# CAN_Termination_Connector.net
KiCad netlist of a schematic drawn in Altium Designer
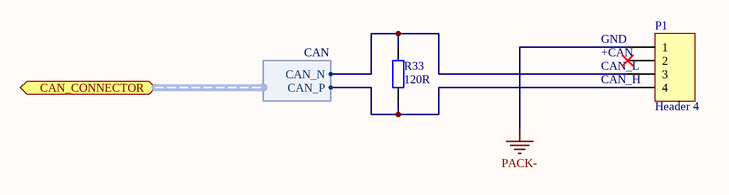
[diagram p0: CAN Termination Connector.SchDoc]

(export (version "E")
  (design (tool "Eeschema 10.0.6"))
  (components
    (comp (ref "P1")
      (value "Header 4")
      (footprint "S04B-PASK-2")
      (description "Header, 4-Pin")
      (fields (field (name "PUBLISHER") "Altium Limited"))
      (libsource (lib "Miscellaneous Connectors") (part "Header 4"))
    )
    (comp (ref "R33")
      (value "120R")
      (footprint "R0603")
      (description "Resistor")
      (fields (field (name "Comment") "Res2") (field (name "PUBLISHER") "Altium Limited"))
      (libsource (lib "Miscellaneous Devices") (part "Res2"))
    )
  )
  (nets
    (net (code "3") (name "Net-(P1-Pad3)") (class "Default")
      (node (ref "P1") (pin "3") (pinfunction "3_3") (pintype "passive"))
      (node (ref "R33") (pin "2") (pinfunction "2_2") (pintype "passive"))
    )
    (net (code "4") (name "Net-(P1-Pad4)") (class "Default")
      (node (ref "P1") (pin "4") (pinfunction "4_4") (pintype "passive"))
      (node (ref "R33") (pin "1") (pinfunction "1_1") (pintype "passive"))
    )
    (net (code "5") (name "PACK-") (class "Default")
      (node (ref "P1") (pin "1") (pinfunction "1_1") (pintype "passive"))
    )
    (net (code "6") (name "unconnected-(P1-Pad2)") (class "Default")
      (node (ref "P1") (pin "2") (pinfunction "2_2") (pintype "passive+no_connect"))
    )
  )
)
